# SCH_Pico-android-remote_2025-09-06.net
KiCad netlist of a schematic drawn in EasyEDA
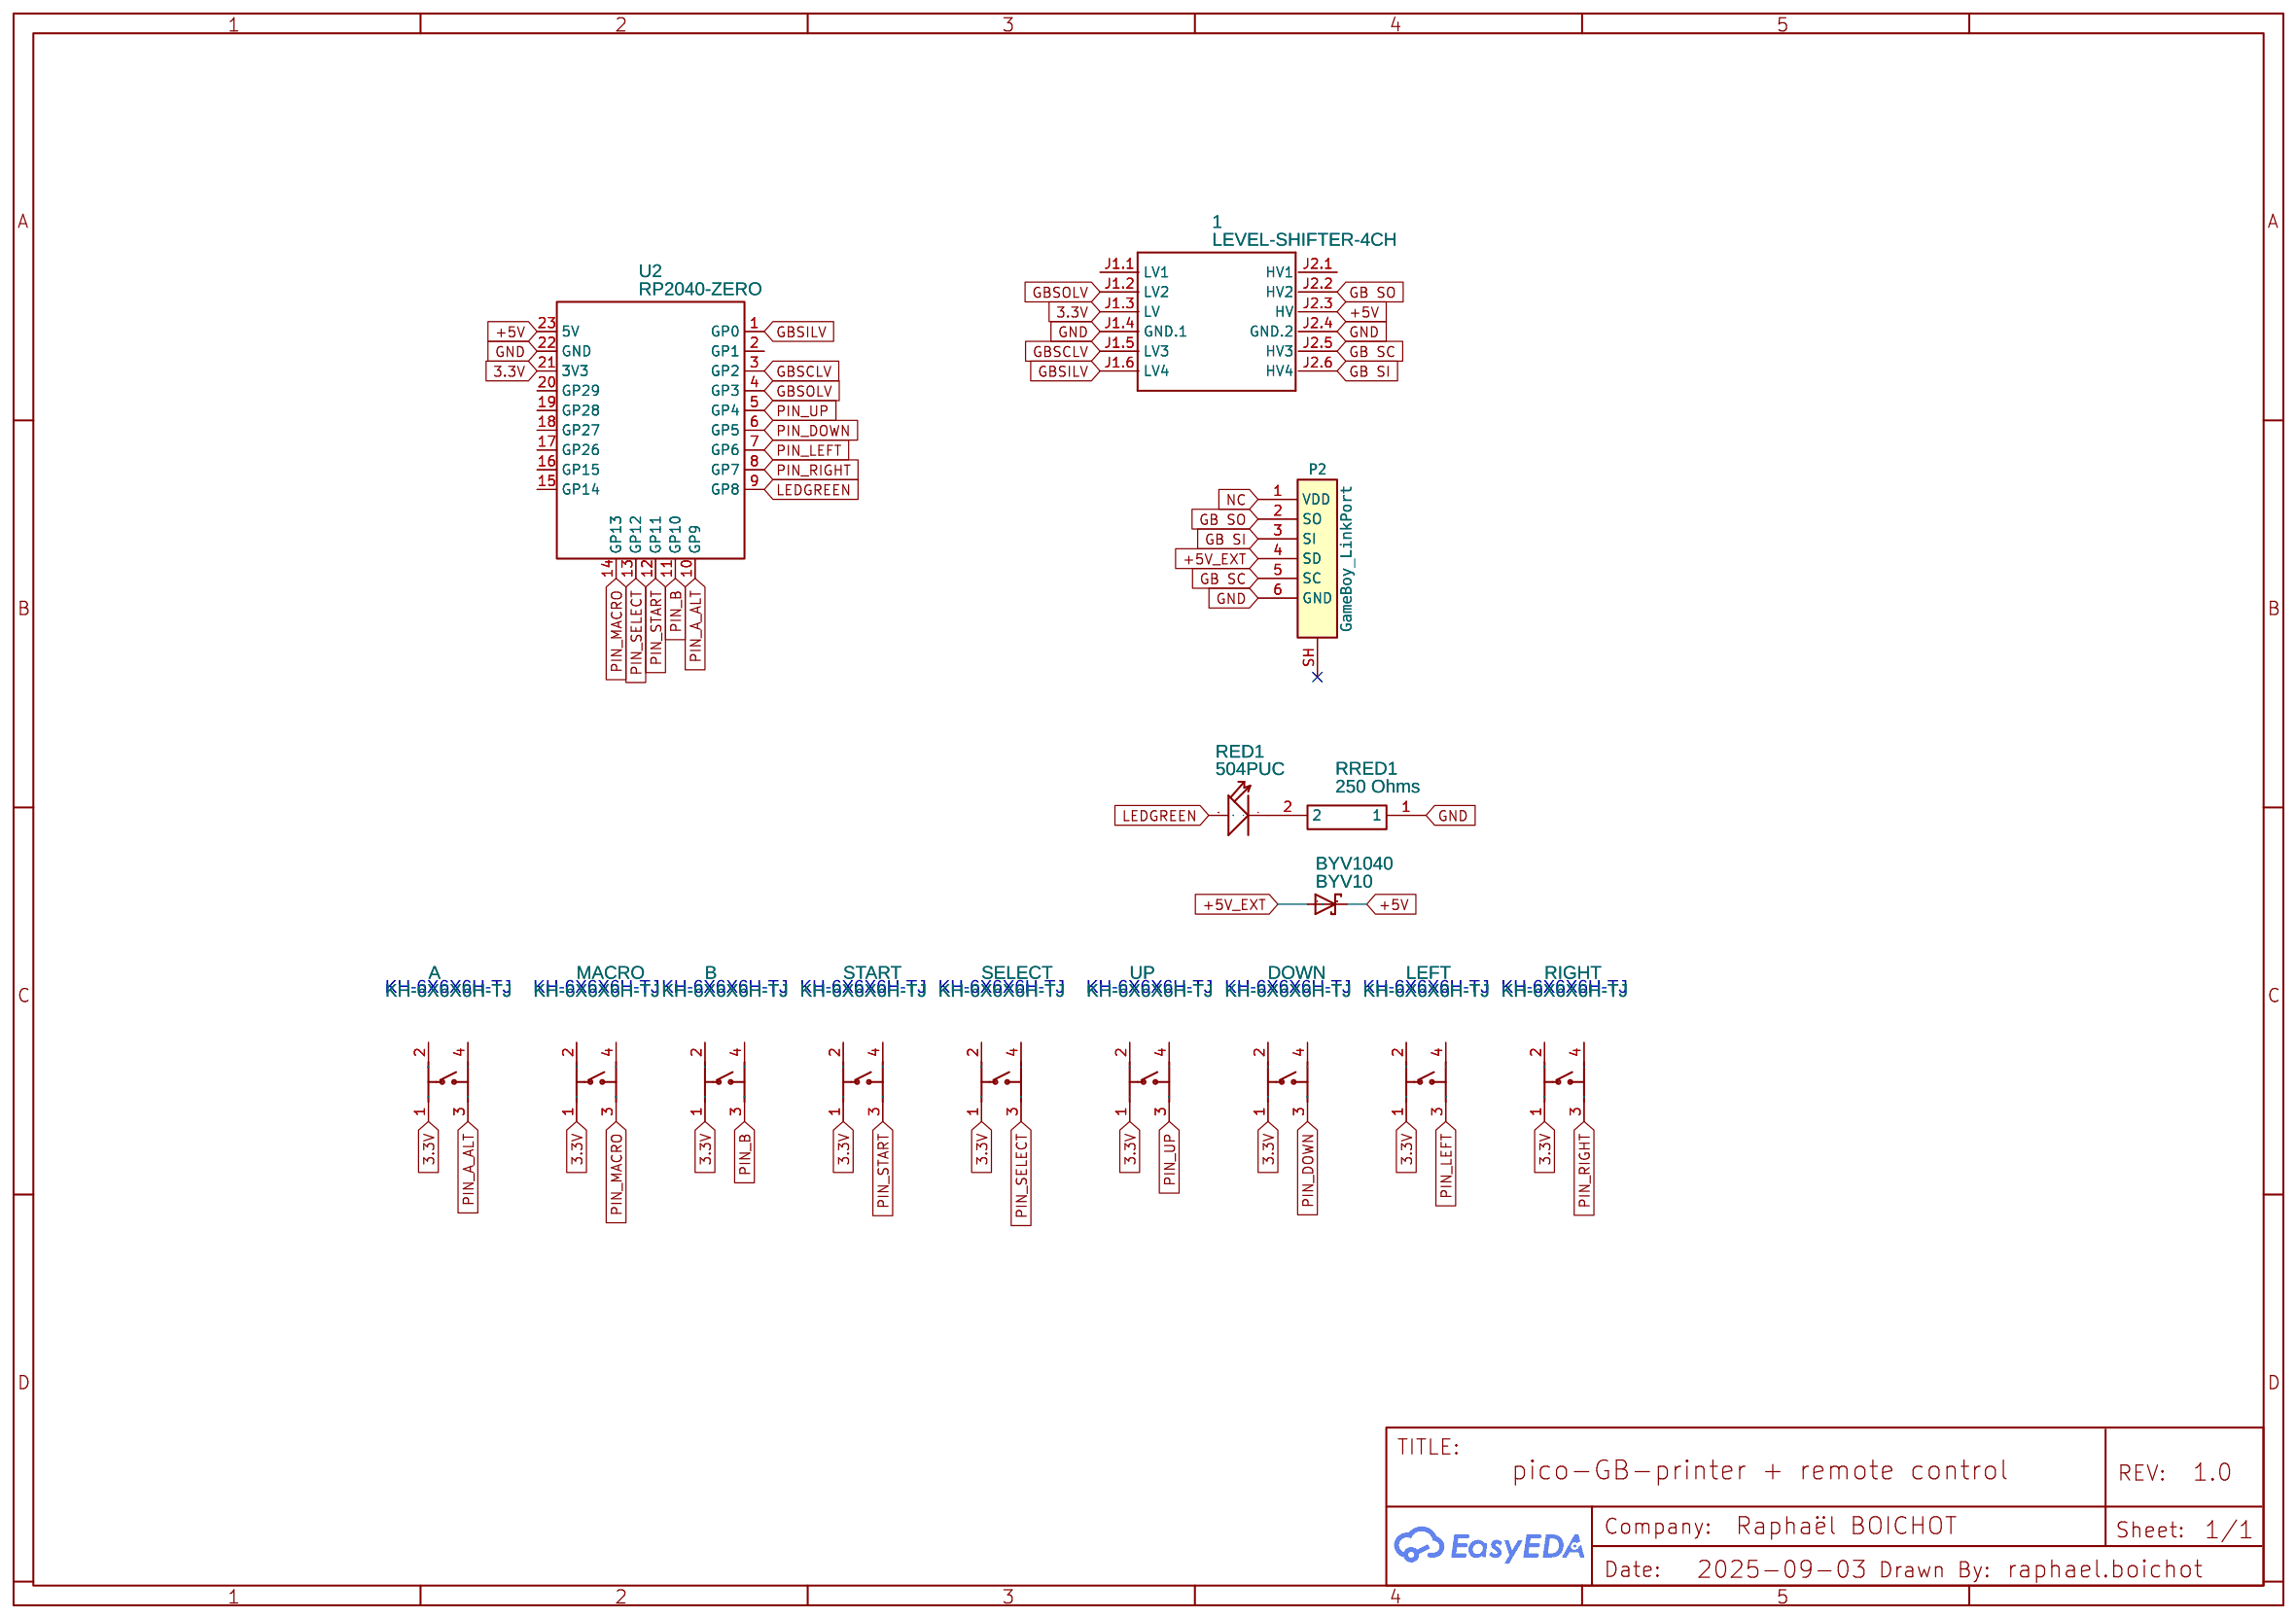
[diagram p0: schematic sheet]

(export (version "E")
  (design (tool "Eeschema 10.0.6"))
  (components
    (comp (ref "1") (value "LEVEL-SHIFTER-4CH") (libsource (lib "") (part "LEVEL-SHIFTER-4CH")))
    (comp (ref "A")
      (value "KH-6X6X6H-TJ")
      (fields (field (name "Manufacturer") "kinghelm(金航标)"))
      (libsource (lib "") (part "KH-6X6X6H-TJ_1"))
    )
    (comp (ref "B")
      (value "KH-6X6X6H-TJ")
      (fields (field (name "Manufacturer") "kinghelm(金航标)"))
      (libsource (lib "") (part "KH-6X6X6H-TJ_2"))
    )
    (comp (ref "BYV1040") (value "BYV10") (libsource (lib "") (part "BYV10")))
    (comp (ref "DOWN")
      (value "KH-6X6X6H-TJ")
      (fields (field (name "Manufacturer") "kinghelm(金航标)"))
      (libsource (lib "") (part "KH-6X6X6H-TJ_8"))
    )
    (comp (ref "LEFT")
      (value "KH-6X6X6H-TJ")
      (fields (field (name "Manufacturer") "kinghelm(金航标)"))
      (libsource (lib "") (part "KH-6X6X6H-TJ"))
    )
    (comp (ref "MACRO")
      (value "KH-6X6X6H-TJ")
      (fields (field (name "Manufacturer") "kinghelm(金航标)"))
      (libsource (lib "") (part "KH-6X6X6H-TJ_4"))
    )
    (comp (ref "P2") (value "GameBoy_LinkPort") (libsource (lib "") (part "Unknown_660_-530")))
    (comp (ref "RED1") (value "504PUC") (libsource (lib "") (part "504PUC")))
    (comp (ref "RIGHT")
      (value "KH-6X6X6H-TJ")
      (fields (field (name "Manufacturer") "kinghelm(金航标)"))
      (libsource (lib "") (part "KH-6X6X6H-TJ_6"))
    )
    (comp (ref "RRED1") (value "250 Ohms") (libsource (lib "") (part "RESITOR")))
    (comp (ref "SELECT")
      (value "KH-6X6X6H-TJ")
      (fields (field (name "Manufacturer") "kinghelm(金航标)"))
      (libsource (lib "") (part "KH-6X6X6H-TJ_5"))
    )
    (comp (ref "START")
      (value "KH-6X6X6H-TJ")
      (fields (field (name "Manufacturer") "kinghelm(金航标)"))
      (libsource (lib "") (part "KH-6X6X6H-TJ_7"))
    )
    (comp (ref "U2") (value "RP2040-ZERO") (libsource (lib "") (part "RP2040-ZERO")))
    (comp (ref "UP")
      (value "KH-6X6X6H-TJ")
      (fields (field (name "Manufacturer") "kinghelm(金航标)"))
      (libsource (lib "") (part "KH-6X6X6H-TJ_3"))
    )
  )
  (nets
    (net (code "1") (name "+5V") (class "Default")
      (node (ref "1") (pin "J2.3") (pinfunction "HV_J2.3") (pintype "bidirectional"))
      (node (ref "BYV1040") (pin "C") (pinfunction "C_C") (pintype "bidirectional"))
      (node (ref "U2") (pin "23") (pinfunction "5V_23") (pintype "unspecified"))
    )
    (net (code "2") (name "+5V_EXT") (class "Default")
      (node (ref "BYV1040") (pin "A") (pinfunction "A_A") (pintype "bidirectional"))
      (node (ref "P2") (pin "4") (pinfunction "SD_4") (pintype "unspecified"))
    )
    (net (code "3") (name "3.3V") (class "Default")
      (node (ref "1") (pin "J1.3") (pinfunction "LV_J1.3") (pintype "bidirectional"))
      (node (ref "A") (pin "1") (pinfunction "1_1") (pintype "unspecified"))
      (node (ref "B") (pin "1") (pinfunction "1_1") (pintype "unspecified"))
      (node (ref "DOWN") (pin "1") (pinfunction "1_1") (pintype "unspecified"))
      (node (ref "LEFT") (pin "1") (pinfunction "1_1") (pintype "unspecified"))
      (node (ref "MACRO") (pin "1") (pinfunction "1_1") (pintype "unspecified"))
      (node (ref "RIGHT") (pin "1") (pinfunction "1_1") (pintype "unspecified"))
      (node (ref "SELECT") (pin "1") (pinfunction "1_1") (pintype "unspecified"))
      (node (ref "START") (pin "1") (pinfunction "1_1") (pintype "unspecified"))
      (node (ref "U2") (pin "21") (pinfunction "3V3_21") (pintype "unspecified"))
      (node (ref "UP") (pin "1") (pinfunction "1_1") (pintype "unspecified"))
    )
    (net (code "4") (name "GB SC") (class "Default")
      (node (ref "1") (pin "J2.5") (pinfunction "HV3_J2.5") (pintype "bidirectional"))
      (node (ref "P2") (pin "5") (pinfunction "SC_5") (pintype "unspecified"))
    )
    (net (code "5") (name "GB SI") (class "Default")
      (node (ref "1") (pin "J2.6") (pinfunction "HV4_J2.6") (pintype "bidirectional"))
      (node (ref "P2") (pin "3") (pinfunction "SI_3") (pintype "unspecified"))
    )
    (net (code "6") (name "GB SO") (class "Default")
      (node (ref "1") (pin "J2.2") (pinfunction "HV2_J2.2") (pintype "bidirectional"))
      (node (ref "P2") (pin "2") (pinfunction "SO_2") (pintype "unspecified"))
    )
    (net (code "7") (name "GBSCLV") (class "Default")
      (node (ref "1") (pin "J1.5") (pinfunction "LV3_J1.5") (pintype "bidirectional"))
      (node (ref "U2") (pin "3") (pinfunction "GP2_3") (pintype "unspecified"))
    )
    (net (code "8") (name "GBSILV") (class "Default")
      (node (ref "1") (pin "J1.6") (pinfunction "LV4_J1.6") (pintype "bidirectional"))
      (node (ref "U2") (pin "1") (pinfunction "GP0_1") (pintype "unspecified"))
    )
    (net (code "9") (name "GBSOLV") (class "Default")
      (node (ref "1") (pin "J1.2") (pinfunction "LV2_J1.2") (pintype "bidirectional"))
      (node (ref "U2") (pin "4") (pinfunction "GP3_4") (pintype "unspecified"))
    )
    (net (code "10") (name "GND") (class "Default")
      (node (ref "1") (pin "J1.4") (pinfunction "GND.1_J1.4") (pintype "bidirectional"))
      (node (ref "1") (pin "J2.4") (pinfunction "GND.2_J2.4") (pintype "bidirectional"))
      (node (ref "P2") (pin "6") (pinfunction "GND_6") (pintype "unspecified"))
      (node (ref "RRED1") (pin "1") (pinfunction "1_1") (pintype "unspecified"))
      (node (ref "U2") (pin "22") (pinfunction "GND_22") (pintype "unspecified"))
    )
    (net (code "11") (name "LEDGREEN") (class "Default")
      (node (ref "RED1") (pin "+") (pinfunction "+_+") (pintype "unspecified"))
      (node (ref "U2") (pin "9") (pinfunction "GP8_9") (pintype "unspecified"))
    )
    (net (code "12") (name "NC") (class "Default")
      (node (ref "P2") (pin "1") (pinfunction "VDD_1") (pintype "unspecified"))
    )
    (net (code "13") (name "Net-(RED1-Pad-)") (class "Default")
      (node (ref "RED1") (pin "-") (pinfunction "-_-") (pintype "unspecified"))
      (node (ref "RRED1") (pin "2") (pinfunction "2_2") (pintype "unspecified"))
    )
    (net (code "14") (name "PIN_A_ALT") (class "Default")
      (node (ref "A") (pin "3") (pinfunction "3_3") (pintype "unspecified"))
      (node (ref "U2") (pin "10") (pinfunction "GP9_10") (pintype "unspecified"))
    )
    (net (code "15") (name "PIN_B") (class "Default")
      (node (ref "B") (pin "3") (pinfunction "3_3") (pintype "unspecified"))
      (node (ref "U2") (pin "11") (pinfunction "GP10_11") (pintype "unspecified"))
    )
    (net (code "16") (name "PIN_DOWN") (class "Default")
      (node (ref "DOWN") (pin "3") (pinfunction "3_3") (pintype "unspecified"))
      (node (ref "U2") (pin "6") (pinfunction "GP5_6") (pintype "unspecified"))
    )
    (net (code "17") (name "PIN_LEFT") (class "Default")
      (node (ref "LEFT") (pin "3") (pinfunction "3_3") (pintype "unspecified"))
      (node (ref "U2") (pin "7") (pinfunction "GP6_7") (pintype "unspecified"))
    )
    (net (code "18") (name "PIN_MACRO") (class "Default")
      (node (ref "MACRO") (pin "3") (pinfunction "3_3") (pintype "unspecified"))
      (node (ref "U2") (pin "14") (pinfunction "GP13_14") (pintype "unspecified"))
    )
    (net (code "19") (name "PIN_RIGHT") (class "Default")
      (node (ref "RIGHT") (pin "3") (pinfunction "3_3") (pintype "unspecified"))
      (node (ref "U2") (pin "8") (pinfunction "GP7_8") (pintype "unspecified"))
    )
    (net (code "20") (name "PIN_SELECT") (class "Default")
      (node (ref "SELECT") (pin "3") (pinfunction "3_3") (pintype "unspecified"))
      (node (ref "U2") (pin "13") (pinfunction "GP12_13") (pintype "unspecified"))
    )
    (net (code "21") (name "PIN_START") (class "Default")
      (node (ref "START") (pin "3") (pinfunction "3_3") (pintype "unspecified"))
      (node (ref "U2") (pin "12") (pinfunction "GP11_12") (pintype "unspecified"))
    )
    (net (code "22") (name "PIN_UP") (class "Default")
      (node (ref "U2") (pin "5") (pinfunction "GP4_5") (pintype "unspecified"))
      (node (ref "UP") (pin "3") (pinfunction "3_3") (pintype "unspecified"))
    )
    (net (code "23") (name "unconnected-(1-HV1-PadJ2.1)") (class "Default")
      (node (ref "1") (pin "J2.1") (pinfunction "HV1_J2.1") (pintype "bidirectional"))
    )
    (net (code "24") (name "unconnected-(1-LV1-PadJ1.1)") (class "Default")
      (node (ref "1") (pin "J1.1") (pinfunction "LV1_J1.1") (pintype "bidirectional"))
    )
    (net (code "25") (name "unconnected-(A-Pad2)") (class "Default")
      (node (ref "A") (pin "2") (pinfunction "2_2") (pintype "unspecified"))
    )
    (net (code "26") (name "unconnected-(A-Pad4)") (class "Default")
      (node (ref "A") (pin "4") (pinfunction "4_4") (pintype "unspecified"))
    )
    (net (code "27") (name "unconnected-(B-Pad2)") (class "Default")
      (node (ref "B") (pin "2") (pinfunction "2_2") (pintype "unspecified"))
    )
    (net (code "28") (name "unconnected-(B-Pad4)") (class "Default")
      (node (ref "B") (pin "4") (pinfunction "4_4") (pintype "unspecified"))
    )
    (net (code "29") (name "unconnected-(DOWN-Pad2)") (class "Default")
      (node (ref "DOWN") (pin "2") (pinfunction "2_2") (pintype "unspecified"))
    )
    (net (code "30") (name "unconnected-(DOWN-Pad4)") (class "Default")
      (node (ref "DOWN") (pin "4") (pinfunction "4_4") (pintype "unspecified"))
    )
    (net (code "31") (name "unconnected-(LEFT-Pad2)") (class "Default")
      (node (ref "LEFT") (pin "2") (pinfunction "2_2") (pintype "unspecified"))
    )
    (net (code "32") (name "unconnected-(LEFT-Pad4)") (class "Default")
      (node (ref "LEFT") (pin "4") (pinfunction "4_4") (pintype "unspecified"))
    )
    (net (code "33") (name "unconnected-(MACRO-Pad2)") (class "Default")
      (node (ref "MACRO") (pin "2") (pinfunction "2_2") (pintype "unspecified"))
    )
    (net (code "34") (name "unconnected-(MACRO-Pad4)") (class "Default")
      (node (ref "MACRO") (pin "4") (pinfunction "4_4") (pintype "unspecified"))
    )
    (net (code "35") (name "unconnected-(P2-PadSH)") (class "Default")
      (node (ref "P2") (pin "SH") (pintype "unspecified+no_connect"))
    )
    (net (code "36") (name "unconnected-(RIGHT-Pad2)") (class "Default")
      (node (ref "RIGHT") (pin "2") (pinfunction "2_2") (pintype "unspecified"))
    )
    (net (code "37") (name "unconnected-(RIGHT-Pad4)") (class "Default")
      (node (ref "RIGHT") (pin "4") (pinfunction "4_4") (pintype "unspecified"))
    )
    (net (code "38") (name "unconnected-(SELECT-Pad2)") (class "Default")
      (node (ref "SELECT") (pin "2") (pinfunction "2_2") (pintype "unspecified"))
    )
    (net (code "39") (name "unconnected-(SELECT-Pad4)") (class "Default")
      (node (ref "SELECT") (pin "4") (pinfunction "4_4") (pintype "unspecified"))
    )
    (net (code "40") (name "unconnected-(START-Pad2)") (class "Default")
      (node (ref "START") (pin "2") (pinfunction "2_2") (pintype "unspecified"))
    )
    (net (code "41") (name "unconnected-(START-Pad4)") (class "Default")
      (node (ref "START") (pin "4") (pinfunction "4_4") (pintype "unspecified"))
    )
    (net (code "42") (name "unconnected-(U2-GP1-Pad2)") (class "Default")
      (node (ref "U2") (pin "2") (pinfunction "GP1_2") (pintype "unspecified"))
    )
    (net (code "43") (name "unconnected-(U2-GP14-Pad15)") (class "Default")
      (node (ref "U2") (pin "15") (pinfunction "GP14_15") (pintype "unspecified"))
    )
    (net (code "44") (name "unconnected-(U2-GP15-Pad16)") (class "Default")
      (node (ref "U2") (pin "16") (pinfunction "GP15_16") (pintype "unspecified"))
    )
    (net (code "45") (name "unconnected-(U2-GP26-Pad17)") (class "Default")
      (node (ref "U2") (pin "17") (pinfunction "GP26_17") (pintype "unspecified"))
    )
    (net (code "46") (name "unconnected-(U2-GP27-Pad18)") (class "Default")
      (node (ref "U2") (pin "18") (pinfunction "GP27_18") (pintype "unspecified"))
    )
    (net (code "47") (name "unconnected-(U2-GP28-Pad19)") (class "Default")
      (node (ref "U2") (pin "19") (pinfunction "GP28_19") (pintype "unspecified"))
    )
    (net (code "48") (name "unconnected-(U2-GP29-Pad20)") (class "Default")
      (node (ref "U2") (pin "20") (pinfunction "GP29_20") (pintype "unspecified"))
    )
    (net (code "49") (name "unconnected-(UP-Pad2)") (class "Default")
      (node (ref "UP") (pin "2") (pinfunction "2_2") (pintype "unspecified"))
    )
    (net (code "50") (name "unconnected-(UP-Pad4)") (class "Default")
      (node (ref "UP") (pin "4") (pinfunction "4_4") (pintype "unspecified"))
    )
  )
)
